# 2CAN_Connectors.net
KiCad netlist of a schematic drawn in Altium Designer
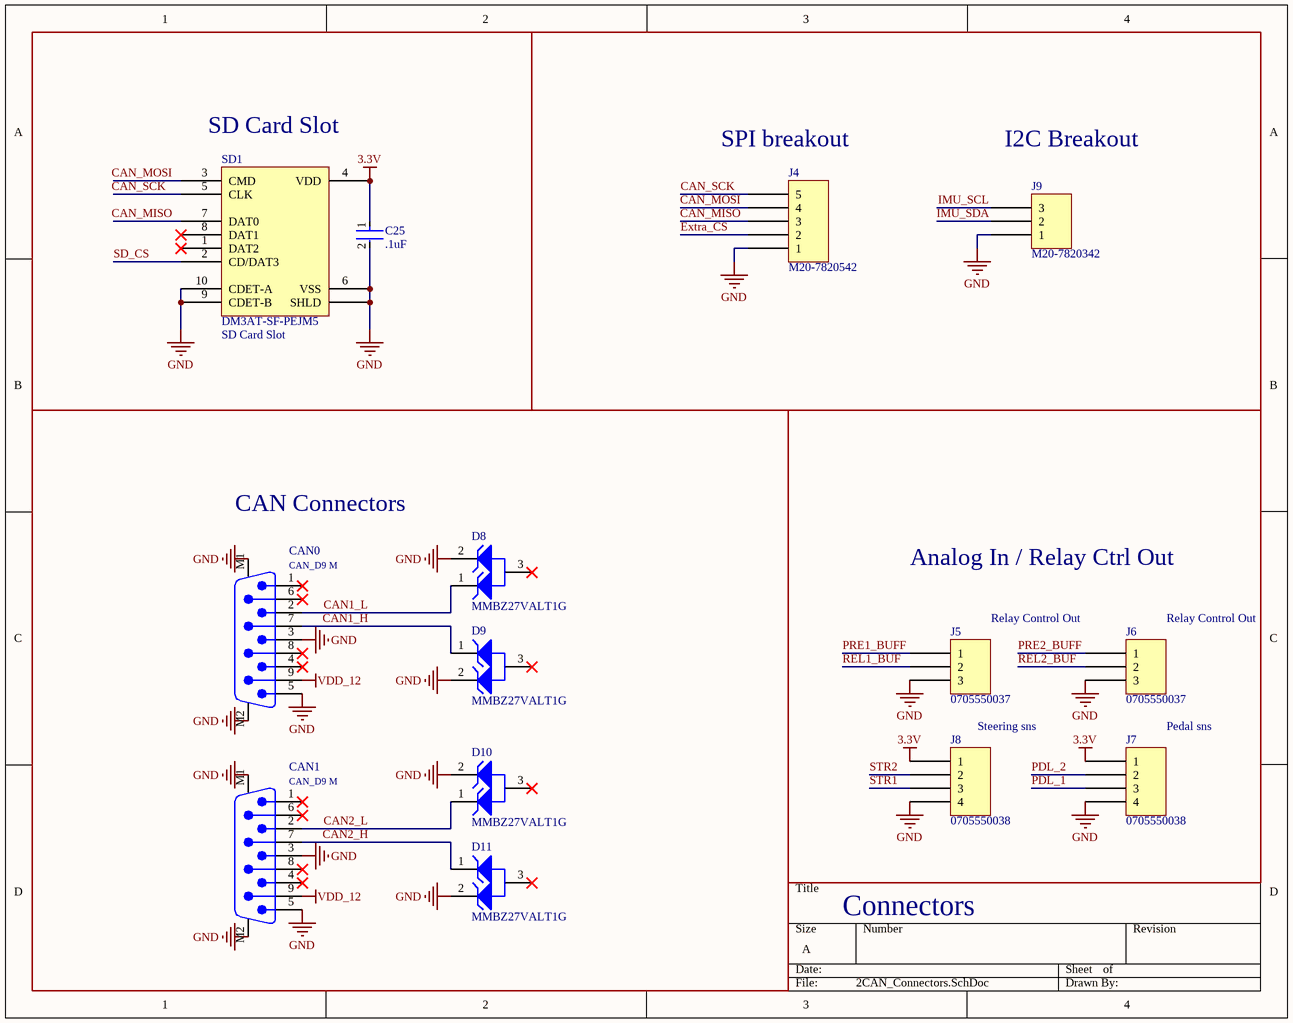
[diagram p0: 2CAN_Connectors.SchDoc]

(export (version "E")
  (design (tool "Eeschema 10.0.6"))
  (components
    (comp (ref "C25")
      (value ".1uF")
      (footprint "FP-CGA3E-0_3-0_1-IPC_A")
      (description "Cap Ceramic 100nF 50V X7R 10% Pad SMD 0603 +125°C Automotive T/R")
      (fields (field (name "TOLERANCE") "10%") (field (name "VOLTAGE") "50V"))
      (libsource (lib "Altium Content Vault") (part "b4654b650e69147ec39a6b967a45e02"))
    )
    (comp (ref "CAN0")
      (value "CAN_D9 M")
      (footprint "618009211721")
      (description "Male PCB Connector without Hex Screw WR-DSUB, 8.08 mm, Angled, 9 pins")
      (fields
        (field (name "PART NUMBER") "618009211721")
        (field (name "MANUFACTURER") "Wurth Elektronik")
        (field (name "PUBLISHER") "WurthElektronik")
      )
      (libsource (lib "Altium Content Vault") (part "WE-CN-2S-2M-D9"))
    )
    (comp (ref "CAN1")
      (value "CAN_D9 M")
      (footprint "618009211721")
      (description "Male PCB Connector without Hex Screw WR-DSUB, 8.08 mm, Angled, 9 pins")
      (fields
        (field (name "PART NUMBER") "618009211721")
        (field (name "MANUFACTURER") "Wurth Elektronik")
        (field (name "PUBLISHER") "WurthElektronik")
      )
      (libsource (lib "Altium Content Vault") (part "WE-CN-2S-2M-D9"))
    )
    (comp (ref "D8")
      (value "MMBZ27VALT1G")
      (footprint "ONSC-SOT-23-3-318-08_V")
      (fields (field (name "MANUFACTURER") "On Semiconductor"))
      (libsource (lib "Altium Content Vault") (part "ONSC-K1K2A3-3"))
    )
    (comp (ref "D9")
      (value "MMBZ27VALT1G")
      (footprint "ONSC-SOT-23-3-318-08_V")
      (fields (field (name "MANUFACTURER") "On Semiconductor"))
      (libsource (lib "Altium Content Vault") (part "ONSC-K1K2A3-3"))
    )
    (comp (ref "D10")
      (value "MMBZ27VALT1G")
      (footprint "ONSC-SOT-23-3-318-08_V")
      (fields (field (name "MANUFACTURER") "On Semiconductor"))
      (libsource (lib "Altium Content Vault") (part "ONSC-K1K2A3-3"))
    )
    (comp (ref "D11")
      (value "MMBZ27VALT1G")
      (footprint "ONSC-SOT-23-3-318-08_V")
      (fields (field (name "MANUFACTURER") "On Semiconductor"))
      (libsource (lib "Altium Content Vault") (part "ONSC-K1K2A3-3"))
    )
    (comp (ref "J4")
      (value "M20-7820542")
      (footprint "HARWIN M20-7820545")
      (description "CONN RCPT 5POS 0.1 GOLD PCB")
      (fields (field (name "MANUFACTURER") "Harwin Inc."))
      (libsource (lib "Celestial Altium Library - altium_library") (part "5 Pin"))
    )
    (comp (ref "J5")
      (value "0705550037")
      (footprint "MOLEX SDA-70555-3PIN")
      (description "CONN HEADER R/A 3POS 2.54MM")
      (fields (field (name "MANUFACTURER") "Molex"))
      (libsource (lib "Celestial Altium Library - altium_library") (part "3 Pin"))
    )
    (comp (ref "J6")
      (value "0705550037")
      (footprint "MOLEX SDA-70555-3PIN")
      (description "CONN HEADER R/A 3POS 2.54MM")
      (fields (field (name "MANUFACTURER") "Molex"))
      (libsource (lib "Celestial Altium Library - altium_library") (part "3 Pin"))
    )
    (comp (ref "J7")
      (value "0705550038")
      (footprint "MOLEX SDA-70555-4PIN")
      (description "CONN HEADER R/A 4POS 2.54MM")
      (fields (field (name "MANUFACTURER") "Molex"))
      (libsource (lib "Celestial Altium Library - altium_library") (part "4 Pin"))
    )
    (comp (ref "J8")
      (value "0705550038")
      (footprint "MOLEX SDA-70555-4PIN")
      (description "CONN HEADER R/A 4POS 2.54MM")
      (fields (field (name "MANUFACTURER") "Molex"))
      (libsource (lib "Celestial Altium Library - altium_library") (part "4 Pin"))
    )
    (comp (ref "J9")
      (value "M20-7820342")
      (footprint "HARWIN M20-7820345")
      (description "CONN RCPT 3POS 0.1 GOLD PCB")
      (fields (field (name "MANUFACTURER") "Harwin Inc."))
      (libsource (lib "") (part "3 Pin_1"))
    )
    (comp (ref "SD1")
      (value "DM3AT-SF-PEJM5")
      (footprint "HIROSE DM3AT-SF-PEJM5")
      (description "CONN MICRO SD CARD PUSH-PUSH R/A")
      (fields (field (name "MANUFACTURER") "Hirose Electric Co Ltd"))
      (libsource (lib "Celestial Altium Library - altium_library") (part "Hirose DM3 MicroSD"))
    )
  )
  (nets
    (net (code "1") (name "/CAN1_H") (class "Default")
      (node (ref "CAN0") (pin "7") (pinfunction "7_7") (pintype "passive"))
      (node (ref "D9") (pin "1") (pinfunction "K1_1") (pintype "passive"))
    )
    (net (code "2") (name "/CAN1_L") (class "Default")
      (node (ref "CAN0") (pin "2") (pinfunction "2_2") (pintype "passive"))
      (node (ref "D8") (pin "1") (pinfunction "K1_1") (pintype "passive"))
    )
    (net (code "3") (name "/CAN2_H") (class "Default")
      (node (ref "CAN1") (pin "7") (pinfunction "7_7") (pintype "passive"))
      (node (ref "D11") (pin "1") (pinfunction "K1_1") (pintype "passive"))
    )
    (net (code "4") (name "/CAN2_L") (class "Default")
      (node (ref "CAN1") (pin "2") (pinfunction "2_2") (pintype "passive"))
      (node (ref "D10") (pin "1") (pinfunction "K1_1") (pintype "passive"))
    )
    (net (code "5") (name "/CAN_MISO") (class "Default")
      (node (ref "J4") (pin "3") (pinfunction "3_3") (pintype "passive"))
      (node (ref "SD1") (pin "7") (pinfunction "DAT0_7") (pintype "passive"))
    )
    (net (code "6") (name "/CAN_MOSI") (class "Default")
      (node (ref "J4") (pin "4") (pinfunction "4_4") (pintype "passive"))
      (node (ref "SD1") (pin "3") (pinfunction "CMD_3") (pintype "passive"))
    )
    (net (code "7") (name "/CAN_SCK") (class "Default")
      (node (ref "J4") (pin "5") (pinfunction "5_5") (pintype "passive"))
      (node (ref "SD1") (pin "5") (pinfunction "CLK_5") (pintype "passive"))
    )
    (net (code "8") (name "/Extra_CS") (class "Default")
      (node (ref "J4") (pin "2") (pinfunction "2_2") (pintype "passive"))
    )
    (net (code "9") (name "/IMU_SCL") (class "Default")
      (node (ref "J9") (pin "3") (pinfunction "3_3") (pintype "passive"))
    )
    (net (code "10") (name "/IMU_SDA") (class "Default")
      (node (ref "J9") (pin "2") (pinfunction "2_2") (pintype "passive"))
    )
    (net (code "11") (name "/PDL_1") (class "Default")
      (node (ref "J7") (pin "3") (pinfunction "3_3") (pintype "passive"))
    )
    (net (code "12") (name "/PDL_2") (class "Default")
      (node (ref "J7") (pin "2") (pinfunction "2_2") (pintype "passive"))
    )
    (net (code "13") (name "/PRE1_BUFF") (class "Default")
      (node (ref "J5") (pin "1") (pinfunction "1_1") (pintype "passive"))
    )
    (net (code "14") (name "/PRE2_BUFF") (class "Default")
      (node (ref "J6") (pin "1") (pinfunction "1_1") (pintype "passive"))
    )
    (net (code "15") (name "/REL1_BUF") (class "Default")
      (node (ref "J5") (pin "2") (pinfunction "2_2") (pintype "passive"))
    )
    (net (code "16") (name "/REL2_BUF") (class "Default")
      (node (ref "J6") (pin "2") (pinfunction "2_2") (pintype "passive"))
    )
    (net (code "17") (name "/SD_CS") (class "Default")
      (node (ref "SD1") (pin "2") (pinfunction "CD/DAT3_2") (pintype "passive"))
    )
    (net (code "18") (name "/STR1") (class "Default")
      (node (ref "J8") (pin "3") (pinfunction "3_3") (pintype "passive"))
    )
    (net (code "19") (name "/STR2") (class "Default")
      (node (ref "J8") (pin "2") (pinfunction "2_2") (pintype "passive"))
    )
    (net (code "20") (name "3.3V") (class "Default")
      (node (ref "C25") (pin "1") (pinfunction "1_1") (pintype "passive"))
      (node (ref "J7") (pin "1") (pinfunction "1_1") (pintype "passive"))
      (node (ref "J8") (pin "1") (pinfunction "1_1") (pintype "passive"))
      (node (ref "SD1") (pin "4") (pinfunction "VDD_4") (pintype "passive"))
    )
    (net (code "21") (name "GND") (class "Default")
      (node (ref "C25") (pin "2") (pinfunction "2_2") (pintype "passive"))
      (node (ref "CAN0") (pin "3") (pinfunction "3_3") (pintype "passive"))
      (node (ref "CAN0") (pin "5") (pinfunction "5_5") (pintype "passive"))
      (node (ref "CAN0") (pin "M1") (pinfunction "M1_M1") (pintype "passive"))
      (node (ref "CAN0") (pin "M2") (pinfunction "M2_M2") (pintype "passive"))
      (node (ref "CAN1") (pin "3") (pinfunction "3_3") (pintype "passive"))
      (node (ref "CAN1") (pin "5") (pinfunction "5_5") (pintype "passive"))
      (node (ref "CAN1") (pin "M1") (pinfunction "M1_M1") (pintype "passive"))
      (node (ref "CAN1") (pin "M2") (pinfunction "M2_M2") (pintype "passive"))
      (node (ref "D10") (pin "2") (pinfunction "K2_2") (pintype "passive"))
      (node (ref "D11") (pin "2") (pinfunction "K2_2") (pintype "passive"))
      (node (ref "D8") (pin "2") (pinfunction "K2_2") (pintype "passive"))
      (node (ref "D9") (pin "2") (pinfunction "K2_2") (pintype "passive"))
      (node (ref "J4") (pin "1") (pinfunction "1_1") (pintype "passive"))
      (node (ref "J5") (pin "3") (pinfunction "3_3") (pintype "passive"))
      (node (ref "J6") (pin "3") (pinfunction "3_3") (pintype "passive"))
      (node (ref "J7") (pin "4") (pinfunction "4_4") (pintype "passive"))
      (node (ref "J8") (pin "4") (pinfunction "4_4") (pintype "passive"))
      (node (ref "J9") (pin "1") (pinfunction "1_1") (pintype "passive"))
      (node (ref "SD1") (pin "10") (pinfunction "CDET-A_10") (pintype "passive"))
      (node (ref "SD1") (pin "6") (pinfunction "VSS_6") (pintype "passive"))
      (node (ref "SD1") (pin "9") (pinfunction "CDET-B_9") (pintype "passive"))
      (node (ref "SD1") (pin "S") (pinfunction "SHLD_S") (pintype "passive"))
    )
    (net (code "22") (name "VDD_12") (class "Default")
      (node (ref "CAN0") (pin "9") (pinfunction "9_9") (pintype "passive"))
      (node (ref "CAN1") (pin "9") (pinfunction "9_9") (pintype "passive"))
    )
    (net (code "23") (name "unconnected-(CAN0-Pad1)") (class "Default")
      (node (ref "CAN0") (pin "1") (pinfunction "1_1") (pintype "passive+no_connect"))
    )
    (net (code "24") (name "unconnected-(CAN0-Pad4)") (class "Default")
      (node (ref "CAN0") (pin "4") (pinfunction "4_4") (pintype "passive+no_connect"))
    )
    (net (code "25") (name "unconnected-(CAN0-Pad6)") (class "Default")
      (node (ref "CAN0") (pin "6") (pinfunction "6_6") (pintype "passive+no_connect"))
    )
    (net (code "26") (name "unconnected-(CAN0-Pad8)") (class "Default")
      (node (ref "CAN0") (pin "8") (pinfunction "8_8") (pintype "passive+no_connect"))
    )
    (net (code "27") (name "unconnected-(CAN1-Pad1)") (class "Default")
      (node (ref "CAN1") (pin "1") (pinfunction "1_1") (pintype "passive+no_connect"))
    )
    (net (code "28") (name "unconnected-(CAN1-Pad4)") (class "Default")
      (node (ref "CAN1") (pin "4") (pinfunction "4_4") (pintype "passive+no_connect"))
    )
    (net (code "29") (name "unconnected-(CAN1-Pad6)") (class "Default")
      (node (ref "CAN1") (pin "6") (pinfunction "6_6") (pintype "passive+no_connect"))
    )
    (net (code "30") (name "unconnected-(CAN1-Pad8)") (class "Default")
      (node (ref "CAN1") (pin "8") (pinfunction "8_8") (pintype "passive+no_connect"))
    )
    (net (code "31") (name "unconnected-(D8-A-Pad3)") (class "Default")
      (node (ref "D8") (pin "3") (pinfunction "A_3") (pintype "passive+no_connect"))
    )
    (net (code "32") (name "unconnected-(D9-A-Pad3)") (class "Default")
      (node (ref "D9") (pin "3") (pinfunction "A_3") (pintype "passive+no_connect"))
    )
    (net (code "33") (name "unconnected-(D10-A-Pad3)") (class "Default")
      (node (ref "D10") (pin "3") (pinfunction "A_3") (pintype "passive+no_connect"))
    )
    (net (code "34") (name "unconnected-(D11-A-Pad3)") (class "Default")
      (node (ref "D11") (pin "3") (pinfunction "A_3") (pintype "passive+no_connect"))
    )
    (net (code "35") (name "unconnected-(SD1-DAT1-Pad8)") (class "Default")
      (node (ref "SD1") (pin "8") (pinfunction "DAT1_8") (pintype "passive+no_connect"))
    )
    (net (code "36") (name "unconnected-(SD1-DAT2-Pad1)") (class "Default")
      (node (ref "SD1") (pin "1") (pinfunction "DAT2_1") (pintype "passive+no_connect"))
    )
  )
)
